# GPS.net
KiCad netlist of a schematic drawn in Altium Designer
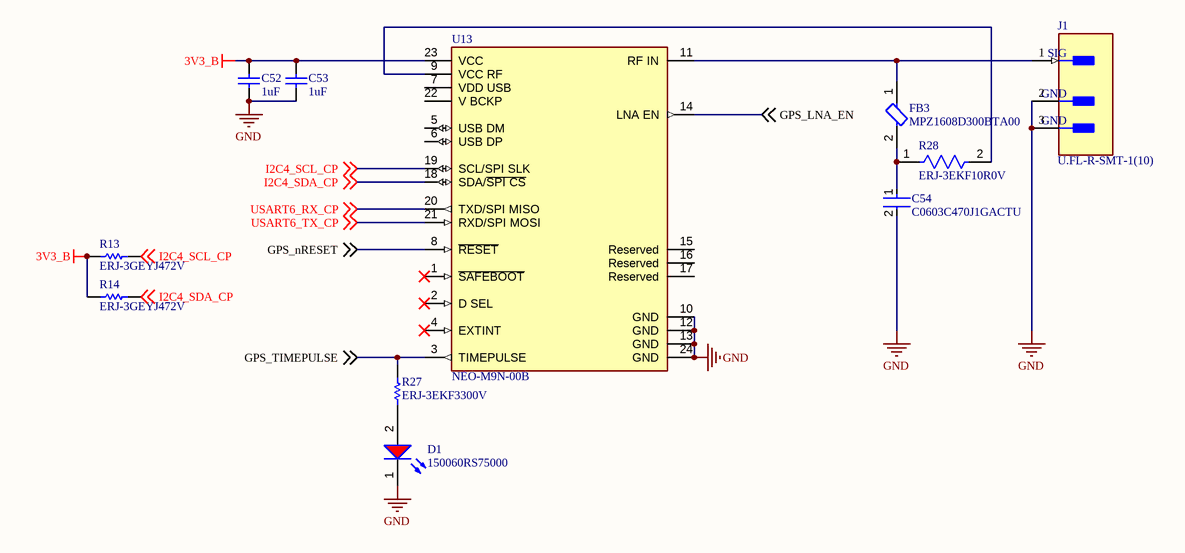
[diagram p0: GPS.SchDoc]

(export (version "E")
  (design (tool "Eeschema 10.0.6"))
  (components
    (comp (ref "C52")
      (value "1uF")
      (footprint "CAPC1608X90X35LL15T15")
      (fields (field (name "MANUFACTURER") "Kemet") (field (name "PART NUMBER") "C0603C105K4RACTU"))
      (libsource (lib "Altium Content Vault") (part "CAP"))
    )
    (comp (ref "C53")
      (value "1uF")
      (footprint "CAPC1608X90X35LL15T15")
      (fields (field (name "MANUFACTURER") "Kemet") (field (name "PART NUMBER") "C0603C105K4RACTU"))
      (libsource (lib "Altium Content Vault") (part "CAP"))
    )
    (comp (ref "C54")
      (value "C0603C470J1GACTU")
      (footprint "FP-C0603C-CF-MFG")
      (description "CAP CER 47PF 100V 5% NP0 0603")
      (fields
        (field (name "MANUFACTURER") "KEMET")
        (field (name "OCTOPART") "https://octopart.com/c0603c470j1gactu-kemet-3768219")
      )
      (libsource (lib "Altium Content Vault") (part "b4654b650e69147ec39a6b967a45e02"))
    )
    (comp (ref "D1")
      (value "150060RS75000")
      (footprint "WL-SMCW_0603_150060xx75000")
      (description "LED Low-Power Uni-Color Red 630nm 2V 2-Pin Chip 0603(1608Metric) T/R")
      (libsource (lib "Altium Content Vault") (part "LED_Red_2A-1K"))
    )
    (comp (ref "FB3")
      (value "MPZ1608D300BTA00")
      (footprint "FP-MPZ1608-0_8-IPC_A")
      (description "FERRITE BEAD 30 OHM 0603 1LN")
      (libsource (lib "Altium Content Vault") (part "5f30dd21d616792df468990f7003faa"))
    )
    (comp (ref "J1")
      (value "U.FL-R-SMT-1(10)")
      (footprint "FP-U_FL-R-SMT-1_10-MFG")
      (description "CONN U.FL RCPT STR 50 OHM SMD")
      (libsource (lib "Altium Content Vault") (part "7158abf7d987fa84906f6fb0d115710"))
    )
    (comp (ref "R13")
      (value "ERJ-3GEYJ472V")
      (footprint "RESC1608X55X30LL15T15")
      (fields (field (name "MANUFACTURER") "Panasonic"))
      (libsource (lib "Altium Content Vault") (part "RES"))
    )
    (comp (ref "R14")
      (value "ERJ-3GEYJ472V")
      (footprint "RESC1608X55X30LL15T15")
      (fields (field (name "MANUFACTURER") "Panasonic"))
      (libsource (lib "Altium Content Vault") (part "RES"))
    )
    (comp (ref "R27")
      (value "ERJ-3EKF3300V")
      (footprint "RESC1608X55X30LL15T15")
      (description "Chip Resistor, 330 Ohm, +/- 1%, 0.1 W, -55 to 155 degC, 0603 (1608 Metric), RoHS, Tape and Reel")
      (libsource (lib "Altium Content Vault") (part "RES-2"))
    )
    (comp (ref "R28")
      (value "ERJ-3EKF10R0V")
      (footprint "FP-ERJ3EK-MFG")
      (description "RES SMD 10 OHM 1% 1/10W 0603")
      (fields
        (field (name "OCTOPART") "https://octopart.com/erj-3ekf10r0v-panasonic-55403649")
        (field (name "MANUFACTURER") "Panasonic")
      )
      (libsource (lib "Altium Content Vault") (part "1029c3af85768c4190bb7ad29bc67b5"))
    )
    (comp (ref "U13")
      (value "NEO-M9N-00B")
      (footprint "FP-NEO-M9N-00B-MFG")
      (description "M9 standard precision module")
      (fields
        (field (name "MANUFACTURER") "u-blox")
        (field (name "OCTOPART") "https://octopart.com/neo-m9n-00b-u-blox-107315722")
      )
      (libsource (lib "Altium Content Vault") (part "6afc83350215ab330c065e89349577f"))
    )
  )
  (nets
    (net (code "1") (name "3V3_B") (class "Default")
      (node (ref "C52") (pin "2") (pinfunction "2_2") (pintype "passive"))
      (node (ref "C53") (pin "2") (pinfunction "2_2") (pintype "passive"))
      (node (ref "R13") (pin "1") (pinfunction "1_1") (pintype "passive"))
      (node (ref "R14") (pin "1") (pinfunction "1_1") (pintype "passive"))
      (node (ref "U13") (pin "23") (pinfunction "VCC_23") (pintype "power_in"))
    )
    (net (code "2") (name "GND") (class "Default")
      (node (ref "C52") (pin "1") (pinfunction "1_1") (pintype "passive"))
      (node (ref "C53") (pin "1") (pinfunction "1_1") (pintype "passive"))
      (node (ref "C54") (pin "2") (pinfunction "2_2") (pintype "passive"))
      (node (ref "D1") (pin "1") (pinfunction "K_1") (pintype "passive"))
      (node (ref "J1") (pin "2") (pinfunction "GND_2") (pintype "power_in"))
      (node (ref "J1") (pin "3") (pinfunction "GND_3") (pintype "power_in"))
      (node (ref "U13") (pin "10") (pinfunction "GND_10") (pintype "power_in"))
      (node (ref "U13") (pin "12") (pinfunction "GND_12") (pintype "power_in"))
      (node (ref "U13") (pin "13") (pinfunction "GND_13") (pintype "power_in"))
      (node (ref "U13") (pin "24") (pinfunction "GND_24") (pintype "power_in"))
    )
    (net (code "3") (name "GPS_LNA_EN") (class "Default")
      (node (ref "U13") (pin "14") (pinfunction "LNA_EN_14") (pintype "output"))
    )
    (net (code "4") (name "GPS_TIMEPULSE") (class "Default")
      (node (ref "R27") (pin "1") (pinfunction "1_1") (pintype "passive"))
      (node (ref "U13") (pin "3") (pinfunction "TIMEPULSE_3") (pintype "output"))
    )
    (net (code "5") (name "GPS_nRESET") (class "Default")
      (node (ref "U13") (pin "8") (pinfunction "~{RESET}_8") (pintype "input"))
    )
    (net (code "6") (name "I2C4_SCL_CP") (class "Default")
      (node (ref "R13") (pin "2") (pinfunction "2_2") (pintype "passive"))
      (node (ref "U13") (pin "19") (pinfunction "SCL/SPI_SLK_19") (pintype "bidirectional"))
    )
    (net (code "7") (name "I2C4_SDA_CP") (class "Default")
      (node (ref "R14") (pin "2") (pinfunction "2_2") (pintype "passive"))
      (node (ref "U13") (pin "18") (pinfunction "SDA/~{SPI_CS}_18") (pintype "bidirectional"))
    )
    (net (code "8") (name "Net-(C54-Pad1)") (class "Default")
      (node (ref "C54") (pin "1") (pinfunction "1_1") (pintype "passive"))
      (node (ref "FB3") (pin "2") (pinfunction "2_2") (pintype "passive"))
      (node (ref "R28") (pin "1") (pinfunction "1_1") (pintype "passive"))
    )
    (net (code "9") (name "Net-(D1-A)") (class "Default")
      (node (ref "D1") (pin "2") (pinfunction "A_2") (pintype "passive"))
      (node (ref "R27") (pin "2") (pinfunction "2_2") (pintype "passive"))
    )
    (net (code "10") (name "Net-(J1-SIG)") (class "Default")
      (node (ref "FB3") (pin "1") (pinfunction "1_1") (pintype "passive"))
      (node (ref "J1") (pin "1") (pinfunction "SIG_1") (pintype "input"))
      (node (ref "U13") (pin "11") (pinfunction "RF_IN_11") (pintype "passive"))
    )
    (net (code "11") (name "Net-(U13-VCC_RF)") (class "Default")
      (node (ref "R28") (pin "2") (pinfunction "2_2") (pintype "passive"))
      (node (ref "U13") (pin "9") (pinfunction "VCC_RF_9") (pintype "power_in"))
    )
    (net (code "12") (name "USART6_RX_CP") (class "Default")
      (node (ref "U13") (pin "20") (pinfunction "TXD/SPI_MISO_20") (pintype "output"))
    )
    (net (code "13") (name "USART6_TX_CP") (class "Default")
      (node (ref "U13") (pin "21") (pinfunction "RXD/SPI_MOSI_21") (pintype "input"))
    )
    (net (code "14") (name "unconnected-(U13-D_SEL-Pad2)") (class "Default")
      (node (ref "U13") (pin "2") (pinfunction "D_SEL_2") (pintype "input+no_connect"))
    )
    (net (code "15") (name "unconnected-(U13-EXTINT-Pad4)") (class "Default")
      (node (ref "U13") (pin "4") (pinfunction "EXTINT_4") (pintype "input+no_connect"))
    )
    (net (code "16") (name "unconnected-(U13-Reserved-Pad15)") (class "Default")
      (node (ref "U13") (pin "15") (pinfunction "Reserved_15") (pintype "passive"))
    )
    (net (code "17") (name "unconnected-(U13-Reserved-Pad16)") (class "Default")
      (node (ref "U13") (pin "16") (pinfunction "Reserved_16") (pintype "passive"))
    )
    (net (code "18") (name "unconnected-(U13-Reserved-Pad17)") (class "Default")
      (node (ref "U13") (pin "17") (pinfunction "Reserved_17") (pintype "passive"))
    )
    (net (code "19") (name "unconnected-(U13-USB_DM-Pad5)") (class "Default")
      (node (ref "U13") (pin "5") (pinfunction "USB_DM_5") (pintype "bidirectional"))
    )
    (net (code "20") (name "unconnected-(U13-USB_DP-Pad6)") (class "Default")
      (node (ref "U13") (pin "6") (pinfunction "USB_DP_6") (pintype "bidirectional"))
    )
    (net (code "21") (name "unconnected-(U13-VDD_USB-Pad7)") (class "Default")
      (node (ref "U13") (pin "7") (pinfunction "VDD_USB_7") (pintype "power_in"))
    )
    (net (code "22") (name "unconnected-(U13-V_BCKP-Pad22)") (class "Default")
      (node (ref "U13") (pin "22") (pinfunction "V_BCKP_22") (pintype "power_in"))
    )
    (net (code "23") (name "unconnected-(U13-~{SAFEBOOT}-Pad1)") (class "Default")
      (node (ref "U13") (pin "1") (pinfunction "~{SAFEBOOT}_1") (pintype "input+no_connect"))
    )
  )
)
